# 549-addon.net
KiCad netlist of a schematic drawn in EAGLE
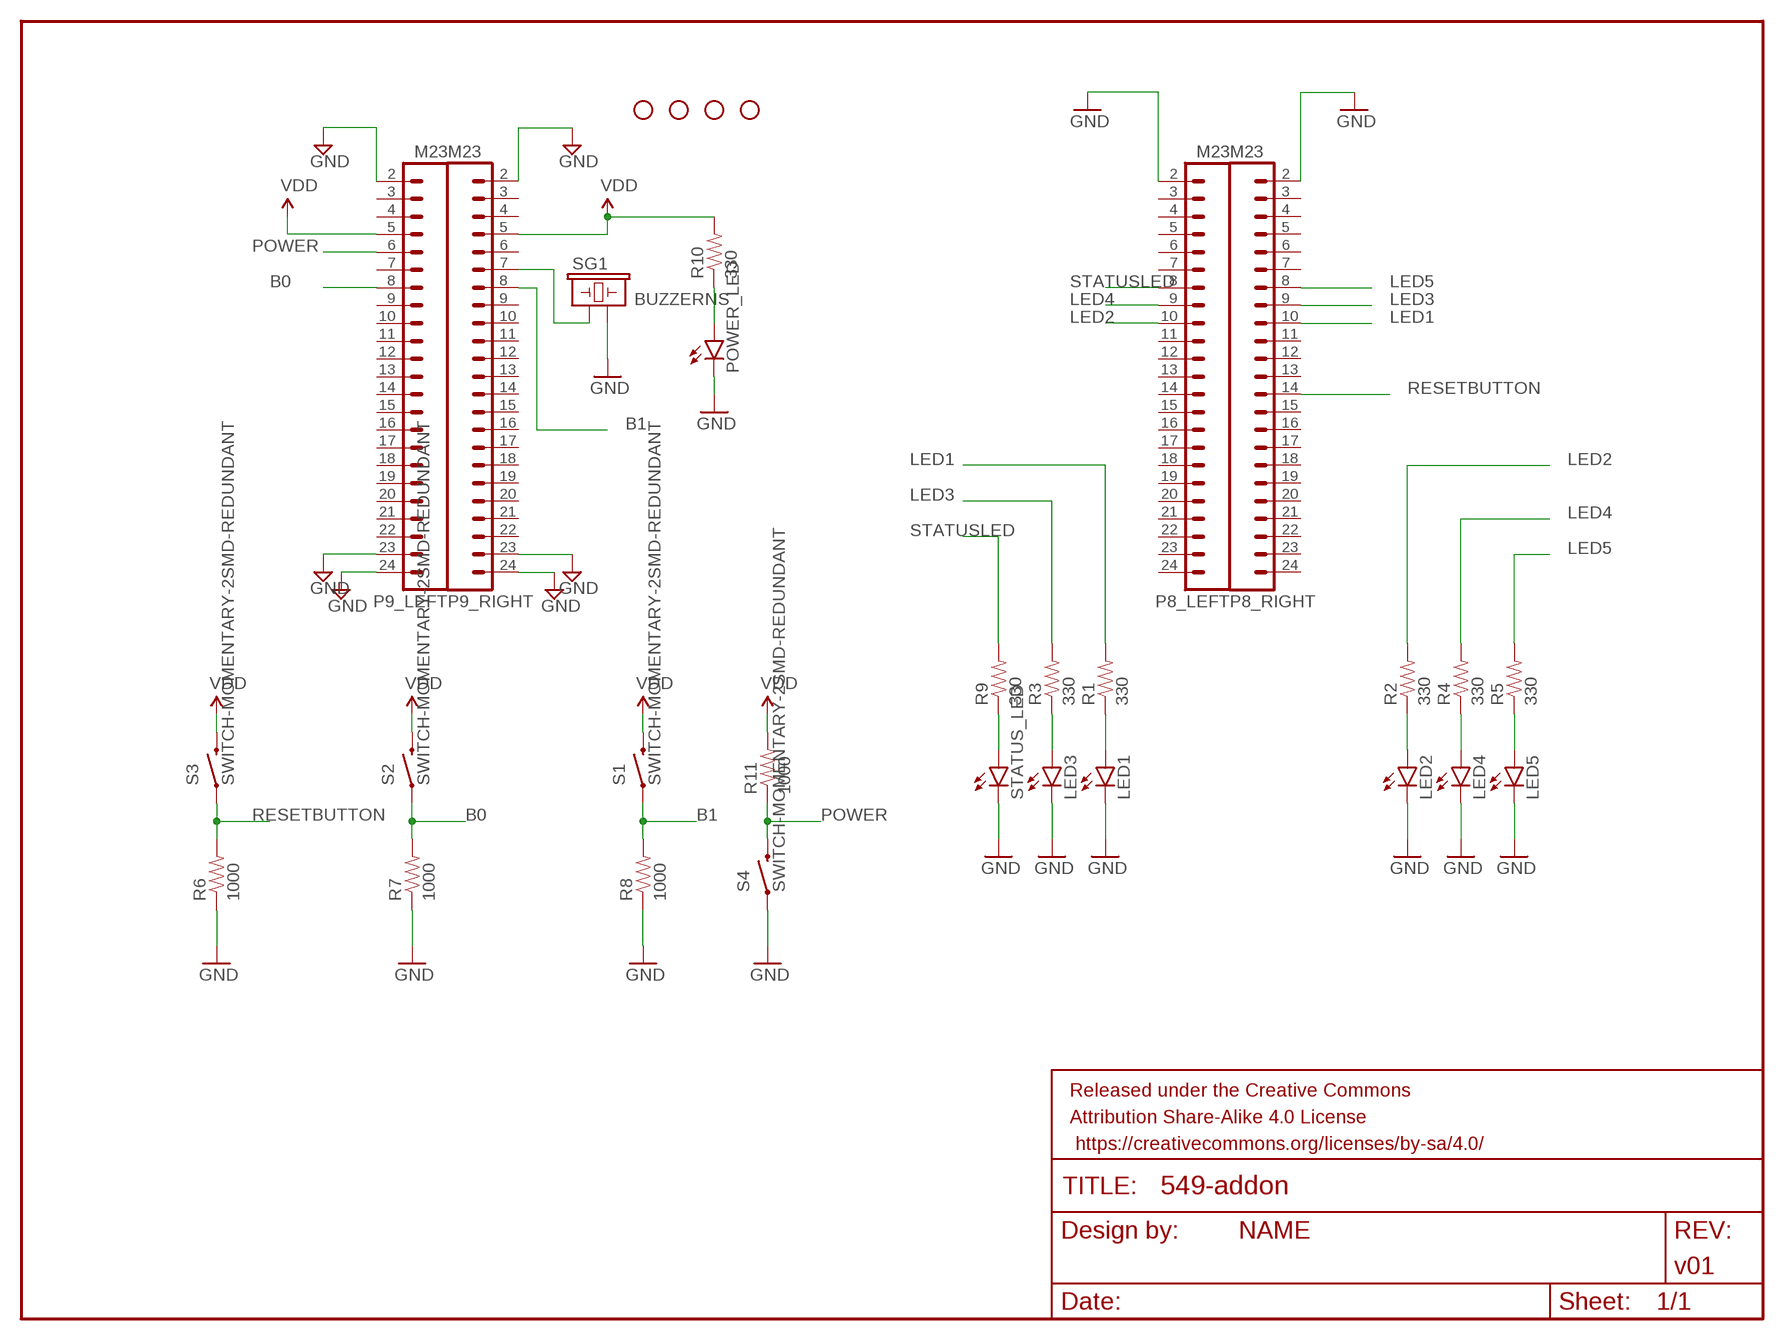
[diagram p0: schematic, sheet 1]

(export (version "E")
  (design (tool "Eeschema 10.0.6"))
  (components
    (comp (ref "FRAME1")
      (value "FRAME-LETTER")
      (footprint "eagle-import:CREATIVE_COMMONS")
      (fields (field (name "DESIGNER") "NAME"))
      (libsource (lib "eagle-import") (part "FRAME-LETTER"))
    )
    (comp (ref "LED1")
      (value "LED1206")
      (footprint "eagle-import:LED-1206")
      (libsource (lib "eagle-import") (part "LED1206"))
    )
    (comp (ref "LED2")
      (value "LED1206")
      (footprint "eagle-import:LED-1206")
      (libsource (lib "eagle-import") (part "LED1206"))
    )
    (comp (ref "LED3")
      (value "LED1206")
      (footprint "eagle-import:LED-1206")
      (libsource (lib "eagle-import") (part "LED1206"))
    )
    (comp (ref "LED4")
      (value "LED1206")
      (footprint "eagle-import:LED-1206")
      (libsource (lib "eagle-import") (part "LED1206"))
    )
    (comp (ref "LED5")
      (value "LED1206")
      (footprint "eagle-import:LED-1206")
      (libsource (lib "eagle-import") (part "LED1206"))
    )
    (comp (ref "P8_LEFT")
      (value "M23")
      (footprint "eagle-import:1X23")
      (libsource (lib "eagle-import") (part "M23"))
    )
    (comp (ref "P8_RIGHT")
      (value "M23")
      (footprint "eagle-import:1X23")
      (libsource (lib "eagle-import") (part "M23"))
    )
    (comp (ref "P9_LEFT")
      (value "M23")
      (footprint "eagle-import:1X23")
      (libsource (lib "eagle-import") (part "M23"))
    )
    (comp (ref "P9_RIGHT")
      (value "M23")
      (footprint "eagle-import:1X23")
      (libsource (lib "eagle-import") (part "M23"))
    )
    (comp (ref "POWER_LED")
      (value "LED1206")
      (footprint "eagle-import:LED-1206")
      (libsource (lib "eagle-import") (part "LED1206"))
    )
    (comp (ref "R1")
      (value "330")
      (footprint "eagle-import:1206")
      (libsource (lib "eagle-import") (part "RESISTOR1206"))
    )
    (comp (ref "R2")
      (value "330")
      (footprint "eagle-import:1206")
      (libsource (lib "eagle-import") (part "RESISTOR1206"))
    )
    (comp (ref "R3")
      (value "330")
      (footprint "eagle-import:1206")
      (libsource (lib "eagle-import") (part "RESISTOR1206"))
    )
    (comp (ref "R4")
      (value "330")
      (footprint "eagle-import:1206")
      (libsource (lib "eagle-import") (part "RESISTOR1206"))
    )
    (comp (ref "R5")
      (value "330")
      (footprint "eagle-import:1206")
      (libsource (lib "eagle-import") (part "RESISTOR1206"))
    )
    (comp (ref "R6")
      (value "1000")
      (footprint "eagle-import:1206")
      (libsource (lib "eagle-import") (part "RESISTOR1206"))
    )
    (comp (ref "R7")
      (value "1000")
      (footprint "eagle-import:1206")
      (libsource (lib "eagle-import") (part "RESISTOR1206"))
    )
    (comp (ref "R8")
      (value "1000")
      (footprint "eagle-import:1206")
      (libsource (lib "eagle-import") (part "RESISTOR1206"))
    )
    (comp (ref "R9")
      (value "330")
      (footprint "eagle-import:1206")
      (libsource (lib "eagle-import") (part "RESISTOR1206"))
    )
    (comp (ref "R10")
      (value "330")
      (footprint "eagle-import:1206")
      (libsource (lib "eagle-import") (part "RESISTOR1206"))
    )
    (comp (ref "R11")
      (value "1000")
      (footprint "eagle-import:1206")
      (libsource (lib "eagle-import") (part "RESISTOR1206"))
    )
    (comp (ref "S1")
      (value "SWITCH-MOMENTARY-2SMD-REDUNDANT")
      (footprint "eagle-import:TACTILE-SWITCH-SMD")
      (libsource (lib "eagle-import") (part "SWITCH-MOMENTARY-2SMD-REDUNDANT"))
    )
    (comp (ref "S2")
      (value "SWITCH-MOMENTARY-2SMD-REDUNDANT")
      (footprint "eagle-import:TACTILE-SWITCH-SMD")
      (libsource (lib "eagle-import") (part "SWITCH-MOMENTARY-2SMD-REDUNDANT"))
    )
    (comp (ref "S3")
      (value "SWITCH-MOMENTARY-2SMD-REDUNDANT")
      (footprint "eagle-import:TACTILE-SWITCH-SMD")
      (libsource (lib "eagle-import") (part "SWITCH-MOMENTARY-2SMD-REDUNDANT"))
    )
    (comp (ref "S4")
      (value "SWITCH-MOMENTARY-2SMD-REDUNDANT")
      (footprint "eagle-import:TACTILE-SWITCH-SMD")
      (libsource (lib "eagle-import") (part "SWITCH-MOMENTARY-2SMD-REDUNDANT"))
    )
    (comp (ref "SG1")
      (value "BUZZERNS")
      (footprint "eagle-import:BUZZER-12MM-NS")
      (libsource (lib "eagle-import") (part "BUZZERNS"))
    )
    (comp (ref "STANDOFF1")
      (value "STAND-OFF")
      (footprint "eagle-import:STAND-OFF")
      (libsource (lib "eagle-import") (part "STAND-OFF"))
    )
    (comp (ref "STANDOFF2")
      (value "STAND-OFF")
      (footprint "eagle-import:STAND-OFF")
      (libsource (lib "eagle-import") (part "STAND-OFF"))
    )
    (comp (ref "STANDOFF3")
      (value "STAND-OFF")
      (footprint "eagle-import:STAND-OFF")
      (libsource (lib "eagle-import") (part "STAND-OFF"))
    )
    (comp (ref "STANDOFF4")
      (value "STAND-OFF")
      (footprint "eagle-import:STAND-OFF")
      (libsource (lib "eagle-import") (part "STAND-OFF"))
    )
    (comp (ref "STATUS_LED")
      (value "LED1206")
      (footprint "eagle-import:LED-1206")
      (libsource (lib "eagle-import") (part "LED1206"))
    )
  )
  (nets
    (net (code "1") (name "/B0") (class "Default")
      (node (ref "P9_LEFT") (pin "8") (pinfunction "8_8") (pintype "passive"))
      (node (ref "R7") (pin "2") (pinfunction "2_2") (pintype "passive"))
      (node (ref "S2") (pin "1") (pinfunction "1_1") (pintype "passive"))
      (node (ref "S2") (pin "2") (pinfunction "1_2") (pintype "passive"))
    )
    (net (code "2") (name "/B1") (class "Default")
      (node (ref "P9_RIGHT") (pin "8") (pinfunction "8_8") (pintype "passive"))
      (node (ref "R8") (pin "2") (pinfunction "2_2") (pintype "passive"))
      (node (ref "S1") (pin "1") (pinfunction "1_1") (pintype "passive"))
      (node (ref "S1") (pin "2") (pinfunction "1_2") (pintype "passive"))
    )
    (net (code "3") (name "/LED1") (class "Default")
      (node (ref "P8_RIGHT") (pin "10") (pinfunction "10_10") (pintype "passive"))
      (node (ref "R1") (pin "2") (pinfunction "2_2") (pintype "passive"))
    )
    (net (code "4") (name "/LED2") (class "Default")
      (node (ref "P8_LEFT") (pin "10") (pinfunction "10_10") (pintype "passive"))
      (node (ref "R2") (pin "2") (pinfunction "2_2") (pintype "passive"))
    )
    (net (code "5") (name "/LED3") (class "Default")
      (node (ref "P8_RIGHT") (pin "9") (pinfunction "9_9") (pintype "passive"))
      (node (ref "R3") (pin "2") (pinfunction "2_2") (pintype "passive"))
    )
    (net (code "6") (name "/LED4") (class "Default")
      (node (ref "P8_LEFT") (pin "9") (pinfunction "9_9") (pintype "passive"))
      (node (ref "R4") (pin "2") (pinfunction "2_2") (pintype "passive"))
    )
    (net (code "7") (name "/LED5") (class "Default")
      (node (ref "P8_RIGHT") (pin "8") (pinfunction "8_8") (pintype "passive"))
      (node (ref "R5") (pin "2") (pinfunction "2_2") (pintype "passive"))
    )
    (net (code "8") (name "/POWER") (class "Default")
      (node (ref "P9_LEFT") (pin "6") (pinfunction "6_6") (pintype "passive"))
      (node (ref "R11") (pin "1") (pinfunction "1_1") (pintype "passive"))
      (node (ref "S4") (pin "3") (pinfunction "2_3") (pintype "passive"))
      (node (ref "S4") (pin "4") (pinfunction "2_4") (pintype "passive"))
    )
    (net (code "9") (name "/RESETBUTTON") (class "Default")
      (node (ref "P8_RIGHT") (pin "14") (pinfunction "14_14") (pintype "passive"))
      (node (ref "R6") (pin "2") (pinfunction "2_2") (pintype "passive"))
      (node (ref "S3") (pin "1") (pinfunction "1_1") (pintype "passive"))
      (node (ref "S3") (pin "2") (pinfunction "1_2") (pintype "passive"))
    )
    (net (code "10") (name "/STATUSLED") (class "Default")
      (node (ref "P8_LEFT") (pin "8") (pinfunction "8_8") (pintype "passive"))
      (node (ref "R9") (pin "2") (pinfunction "2_2") (pintype "passive"))
    )
    (net (code "11") (name "GND") (class "Default")
      (node (ref "LED1") (pin "C") (pinfunction "C_C") (pintype "passive"))
      (node (ref "LED2") (pin "C") (pinfunction "C_C") (pintype "passive"))
      (node (ref "LED3") (pin "C") (pinfunction "C_C") (pintype "passive"))
      (node (ref "LED4") (pin "C") (pinfunction "C_C") (pintype "passive"))
      (node (ref "LED5") (pin "C") (pinfunction "C_C") (pintype "passive"))
      (node (ref "P8_LEFT") (pin "2") (pinfunction "2_2") (pintype "passive"))
      (node (ref "P8_RIGHT") (pin "2") (pinfunction "2_2") (pintype "passive"))
      (node (ref "P9_LEFT") (pin "2") (pinfunction "2_2") (pintype "passive"))
      (node (ref "P9_LEFT") (pin "23") (pinfunction "23_23") (pintype "passive"))
      (node (ref "P9_LEFT") (pin "24") (pinfunction "24_24") (pintype "passive"))
      (node (ref "P9_RIGHT") (pin "2") (pinfunction "2_2") (pintype "passive"))
      (node (ref "P9_RIGHT") (pin "23") (pinfunction "23_23") (pintype "passive"))
      (node (ref "P9_RIGHT") (pin "24") (pinfunction "24_24") (pintype "passive"))
      (node (ref "POWER_LED") (pin "C") (pinfunction "C_C") (pintype "passive"))
      (node (ref "R6") (pin "1") (pinfunction "1_1") (pintype "passive"))
      (node (ref "R7") (pin "1") (pinfunction "1_1") (pintype "passive"))
      (node (ref "R8") (pin "1") (pinfunction "1_1") (pintype "passive"))
      (node (ref "S4") (pin "1") (pinfunction "1_1") (pintype "passive"))
      (node (ref "S4") (pin "2") (pinfunction "1_2") (pintype "passive"))
      (node (ref "SG1") (pin "-") (pinfunction "2_-") (pintype "passive"))
      (node (ref "STATUS_LED") (pin "C") (pinfunction "C_C") (pintype "passive"))
    )
    (net (code "12") (name "Net-(LED1-PadA)") (class "Default")
      (node (ref "LED1") (pin "A") (pinfunction "A_A") (pintype "passive"))
      (node (ref "R1") (pin "1") (pinfunction "1_1") (pintype "passive"))
    )
    (net (code "13") (name "Net-(LED2-PadA)") (class "Default")
      (node (ref "LED2") (pin "A") (pinfunction "A_A") (pintype "passive"))
      (node (ref "R2") (pin "1") (pinfunction "1_1") (pintype "passive"))
    )
    (net (code "14") (name "Net-(LED3-PadA)") (class "Default")
      (node (ref "LED3") (pin "A") (pinfunction "A_A") (pintype "passive"))
      (node (ref "R3") (pin "1") (pinfunction "1_1") (pintype "passive"))
    )
    (net (code "15") (name "Net-(LED4-PadA)") (class "Default")
      (node (ref "LED4") (pin "A") (pinfunction "A_A") (pintype "passive"))
      (node (ref "R4") (pin "1") (pinfunction "1_1") (pintype "passive"))
    )
    (net (code "16") (name "Net-(LED5-PadA)") (class "Default")
      (node (ref "LED5") (pin "A") (pinfunction "A_A") (pintype "passive"))
      (node (ref "R5") (pin "1") (pinfunction "1_1") (pintype "passive"))
    )
    (net (code "17") (name "Net-(POWER_LED-PadA)") (class "Default")
      (node (ref "POWER_LED") (pin "A") (pinfunction "A_A") (pintype "passive"))
      (node (ref "R10") (pin "1") (pinfunction "1_1") (pintype "passive"))
    )
    (net (code "18") (name "Net-(R9-Pad1)") (class "Default")
      (node (ref "R9") (pin "1") (pinfunction "1_1") (pintype "passive"))
      (node (ref "STATUS_LED") (pin "A") (pinfunction "A_A") (pintype "passive"))
    )
    (net (code "19") (name "Net-(SG1-1)") (class "Default")
      (node (ref "P9_RIGHT") (pin "7") (pinfunction "7_7") (pintype "passive"))
      (node (ref "SG1") (pin "+") (pinfunction "1_+") (pintype "passive"))
    )
    (net (code "20") (name "VDD") (class "Default")
      (node (ref "P9_LEFT") (pin "5") (pinfunction "5_5") (pintype "passive"))
      (node (ref "P9_RIGHT") (pin "5") (pinfunction "5_5") (pintype "passive"))
      (node (ref "R10") (pin "2") (pinfunction "2_2") (pintype "passive"))
      (node (ref "R11") (pin "2") (pinfunction "2_2") (pintype "passive"))
      (node (ref "S1") (pin "3") (pinfunction "2_3") (pintype "passive"))
      (node (ref "S1") (pin "4") (pinfunction "2_4") (pintype "passive"))
      (node (ref "S2") (pin "3") (pinfunction "2_3") (pintype "passive"))
      (node (ref "S2") (pin "4") (pinfunction "2_4") (pintype "passive"))
      (node (ref "S3") (pin "3") (pinfunction "2_3") (pintype "passive"))
      (node (ref "S3") (pin "4") (pinfunction "2_4") (pintype "passive"))
    )
    (net (code "21") (name "unconnected-(P8_LEFT-Pad3)") (class "Default")
      (node (ref "P8_LEFT") (pin "3") (pinfunction "3_3") (pintype "passive"))
    )
    (net (code "22") (name "unconnected-(P8_LEFT-Pad4)") (class "Default")
      (node (ref "P8_LEFT") (pin "4") (pinfunction "4_4") (pintype "passive"))
    )
    (net (code "23") (name "unconnected-(P8_LEFT-Pad5)") (class "Default")
      (node (ref "P8_LEFT") (pin "5") (pinfunction "5_5") (pintype "passive"))
    )
    (net (code "24") (name "unconnected-(P8_LEFT-Pad6)") (class "Default")
      (node (ref "P8_LEFT") (pin "6") (pinfunction "6_6") (pintype "passive"))
    )
    (net (code "25") (name "unconnected-(P8_LEFT-Pad7)") (class "Default")
      (node (ref "P8_LEFT") (pin "7") (pinfunction "7_7") (pintype "passive"))
    )
    (net (code "26") (name "unconnected-(P8_LEFT-Pad11)") (class "Default")
      (node (ref "P8_LEFT") (pin "11") (pinfunction "11_11") (pintype "passive"))
    )
    (net (code "27") (name "unconnected-(P8_LEFT-Pad12)") (class "Default")
      (node (ref "P8_LEFT") (pin "12") (pinfunction "12_12") (pintype "passive"))
    )
    (net (code "28") (name "unconnected-(P8_LEFT-Pad13)") (class "Default")
      (node (ref "P8_LEFT") (pin "13") (pinfunction "13_13") (pintype "passive"))
    )
    (net (code "29") (name "unconnected-(P8_LEFT-Pad14)") (class "Default")
      (node (ref "P8_LEFT") (pin "14") (pinfunction "14_14") (pintype "passive"))
    )
    (net (code "30") (name "unconnected-(P8_LEFT-Pad15)") (class "Default")
      (node (ref "P8_LEFT") (pin "15") (pinfunction "15_15") (pintype "passive"))
    )
    (net (code "31") (name "unconnected-(P8_LEFT-Pad16)") (class "Default")
      (node (ref "P8_LEFT") (pin "16") (pinfunction "16_16") (pintype "passive"))
    )
    (net (code "32") (name "unconnected-(P8_LEFT-Pad17)") (class "Default")
      (node (ref "P8_LEFT") (pin "17") (pinfunction "17_17") (pintype "passive"))
    )
    (net (code "33") (name "unconnected-(P8_LEFT-Pad18)") (class "Default")
      (node (ref "P8_LEFT") (pin "18") (pinfunction "18_18") (pintype "passive"))
    )
    (net (code "34") (name "unconnected-(P8_LEFT-Pad19)") (class "Default")
      (node (ref "P8_LEFT") (pin "19") (pinfunction "19_19") (pintype "passive"))
    )
    (net (code "35") (name "unconnected-(P8_LEFT-Pad20)") (class "Default")
      (node (ref "P8_LEFT") (pin "20") (pinfunction "20_20") (pintype "passive"))
    )
    (net (code "36") (name "unconnected-(P8_LEFT-Pad21)") (class "Default")
      (node (ref "P8_LEFT") (pin "21") (pinfunction "21_21") (pintype "passive"))
    )
    (net (code "37") (name "unconnected-(P8_LEFT-Pad22)") (class "Default")
      (node (ref "P8_LEFT") (pin "22") (pinfunction "22_22") (pintype "passive"))
    )
    (net (code "38") (name "unconnected-(P8_LEFT-Pad23)") (class "Default")
      (node (ref "P8_LEFT") (pin "23") (pinfunction "23_23") (pintype "passive"))
    )
    (net (code "39") (name "unconnected-(P8_LEFT-Pad24)") (class "Default")
      (node (ref "P8_LEFT") (pin "24") (pinfunction "24_24") (pintype "passive"))
    )
    (net (code "40") (name "unconnected-(P8_RIGHT-Pad3)") (class "Default")
      (node (ref "P8_RIGHT") (pin "3") (pinfunction "3_3") (pintype "passive"))
    )
    (net (code "41") (name "unconnected-(P8_RIGHT-Pad4)") (class "Default")
      (node (ref "P8_RIGHT") (pin "4") (pinfunction "4_4") (pintype "passive"))
    )
    (net (code "42") (name "unconnected-(P8_RIGHT-Pad5)") (class "Default")
      (node (ref "P8_RIGHT") (pin "5") (pinfunction "5_5") (pintype "passive"))
    )
    (net (code "43") (name "unconnected-(P8_RIGHT-Pad6)") (class "Default")
      (node (ref "P8_RIGHT") (pin "6") (pinfunction "6_6") (pintype "passive"))
    )
    (net (code "44") (name "unconnected-(P8_RIGHT-Pad7)") (class "Default")
      (node (ref "P8_RIGHT") (pin "7") (pinfunction "7_7") (pintype "passive"))
    )
    (net (code "45") (name "unconnected-(P8_RIGHT-Pad11)") (class "Default")
      (node (ref "P8_RIGHT") (pin "11") (pinfunction "11_11") (pintype "passive"))
    )
    (net (code "46") (name "unconnected-(P8_RIGHT-Pad12)") (class "Default")
      (node (ref "P8_RIGHT") (pin "12") (pinfunction "12_12") (pintype "passive"))
    )
    (net (code "47") (name "unconnected-(P8_RIGHT-Pad13)") (class "Default")
      (node (ref "P8_RIGHT") (pin "13") (pinfunction "13_13") (pintype "passive"))
    )
    (net (code "48") (name "unconnected-(P8_RIGHT-Pad15)") (class "Default")
      (node (ref "P8_RIGHT") (pin "15") (pinfunction "15_15") (pintype "passive"))
    )
    (net (code "49") (name "unconnected-(P8_RIGHT-Pad16)") (class "Default")
      (node (ref "P8_RIGHT") (pin "16") (pinfunction "16_16") (pintype "passive"))
    )
    (net (code "50") (name "unconnected-(P8_RIGHT-Pad17)") (class "Default")
      (node (ref "P8_RIGHT") (pin "17") (pinfunction "17_17") (pintype "passive"))
    )
    (net (code "51") (name "unconnected-(P8_RIGHT-Pad18)") (class "Default")
      (node (ref "P8_RIGHT") (pin "18") (pinfunction "18_18") (pintype "passive"))
    )
    (net (code "52") (name "unconnected-(P8_RIGHT-Pad19)") (class "Default")
      (node (ref "P8_RIGHT") (pin "19") (pinfunction "19_19") (pintype "passive"))
    )
    (net (code "53") (name "unconnected-(P8_RIGHT-Pad20)") (class "Default")
      (node (ref "P8_RIGHT") (pin "20") (pinfunction "20_20") (pintype "passive"))
    )
    (net (code "54") (name "unconnected-(P8_RIGHT-Pad21)") (class "Default")
      (node (ref "P8_RIGHT") (pin "21") (pinfunction "21_21") (pintype "passive"))
    )
    (net (code "55") (name "unconnected-(P8_RIGHT-Pad22)") (class "Default")
      (node (ref "P8_RIGHT") (pin "22") (pinfunction "22_22") (pintype "passive"))
    )
    (net (code "56") (name "unconnected-(P8_RIGHT-Pad23)") (class "Default")
      (node (ref "P8_RIGHT") (pin "23") (pinfunction "23_23") (pintype "passive"))
    )
    (net (code "57") (name "unconnected-(P8_RIGHT-Pad24)") (class "Default")
      (node (ref "P8_RIGHT") (pin "24") (pinfunction "24_24") (pintype "passive"))
    )
    (net (code "58") (name "unconnected-(P9_LEFT-Pad3)") (class "Default")
      (node (ref "P9_LEFT") (pin "3") (pinfunction "3_3") (pintype "passive"))
    )
    (net (code "59") (name "unconnected-(P9_LEFT-Pad4)") (class "Default")
      (node (ref "P9_LEFT") (pin "4") (pinfunction "4_4") (pintype "passive"))
    )
    (net (code "60") (name "unconnected-(P9_LEFT-Pad7)") (class "Default")
      (node (ref "P9_LEFT") (pin "7") (pinfunction "7_7") (pintype "passive"))
    )
    (net (code "61") (name "unconnected-(P9_LEFT-Pad9)") (class "Default")
      (node (ref "P9_LEFT") (pin "9") (pinfunction "9_9") (pintype "passive"))
    )
    (net (code "62") (name "unconnected-(P9_LEFT-Pad10)") (class "Default")
      (node (ref "P9_LEFT") (pin "10") (pinfunction "10_10") (pintype "passive"))
    )
    (net (code "63") (name "unconnected-(P9_LEFT-Pad11)") (class "Default")
      (node (ref "P9_LEFT") (pin "11") (pinfunction "11_11") (pintype "passive"))
    )
    (net (code "64") (name "unconnected-(P9_LEFT-Pad12)") (class "Default")
      (node (ref "P9_LEFT") (pin "12") (pinfunction "12_12") (pintype "passive"))
    )
    (net (code "65") (name "unconnected-(P9_LEFT-Pad13)") (class "Default")
      (node (ref "P9_LEFT") (pin "13") (pinfunction "13_13") (pintype "passive"))
    )
    (net (code "66") (name "unconnected-(P9_LEFT-Pad14)") (class "Default")
      (node (ref "P9_LEFT") (pin "14") (pinfunction "14_14") (pintype "passive"))
    )
    (net (code "67") (name "unconnected-(P9_LEFT-Pad15)") (class "Default")
      (node (ref "P9_LEFT") (pin "15") (pinfunction "15_15") (pintype "passive"))
    )
    (net (code "68") (name "unconnected-(P9_LEFT-Pad16)") (class "Default")
      (node (ref "P9_LEFT") (pin "16") (pinfunction "16_16") (pintype "passive"))
    )
    (net (code "69") (name "unconnected-(P9_LEFT-Pad17)") (class "Default")
      (node (ref "P9_LEFT") (pin "17") (pinfunction "17_17") (pintype "passive"))
    )
    (net (code "70") (name "unconnected-(P9_LEFT-Pad18)") (class "Default")
      (node (ref "P9_LEFT") (pin "18") (pinfunction "18_18") (pintype "passive"))
    )
    (net (code "71") (name "unconnected-(P9_LEFT-Pad19)") (class "Default")
      (node (ref "P9_LEFT") (pin "19") (pinfunction "19_19") (pintype "passive"))
    )
    (net (code "72") (name "unconnected-(P9_LEFT-Pad20)") (class "Default")
      (node (ref "P9_LEFT") (pin "20") (pinfunction "20_20") (pintype "passive"))
    )
    (net (code "73") (name "unconnected-(P9_LEFT-Pad21)") (class "Default")
      (node (ref "P9_LEFT") (pin "21") (pinfunction "21_21") (pintype "passive"))
    )
    (net (code "74") (name "unconnected-(P9_LEFT-Pad22)") (class "Default")
      (node (ref "P9_LEFT") (pin "22") (pinfunction "22_22") (pintype "passive"))
    )
    (net (code "75") (name "unconnected-(P9_RIGHT-Pad3)") (class "Default")
      (node (ref "P9_RIGHT") (pin "3") (pinfunction "3_3") (pintype "passive"))
    )
    (net (code "76") (name "unconnected-(P9_RIGHT-Pad4)") (class "Default")
      (node (ref "P9_RIGHT") (pin "4") (pinfunction "4_4") (pintype "passive"))
    )
    (net (code "77") (name "unconnected-(P9_RIGHT-Pad6)") (class "Default")
      (node (ref "P9_RIGHT") (pin "6") (pinfunction "6_6") (pintype "passive"))
    )
    (net (code "78") (name "unconnected-(P9_RIGHT-Pad9)") (class "Default")
      (node (ref "P9_RIGHT") (pin "9") (pinfunction "9_9") (pintype "passive"))
    )
    (net (code "79") (name "unconnected-(P9_RIGHT-Pad10)") (class "Default")
      (node (ref "P9_RIGHT") (pin "10") (pinfunction "10_10") (pintype "passive"))
    )
    (net (code "80") (name "unconnected-(P9_RIGHT-Pad11)") (class "Default")
      (node (ref "P9_RIGHT") (pin "11") (pinfunction "11_11") (pintype "passive"))
    )
    (net (code "81") (name "unconnected-(P9_RIGHT-Pad12)") (class "Default")
      (node (ref "P9_RIGHT") (pin "12") (pinfunction "12_12") (pintype "passive"))
    )
    (net (code "82") (name "unconnected-(P9_RIGHT-Pad13)") (class "Default")
      (node (ref "P9_RIGHT") (pin "13") (pinfunction "13_13") (pintype "passive"))
    )
    (net (code "83") (name "unconnected-(P9_RIGHT-Pad14)") (class "Default")
      (node (ref "P9_RIGHT") (pin "14") (pinfunction "14_14") (pintype "passive"))
    )
    (net (code "84") (name "unconnected-(P9_RIGHT-Pad15)") (class "Default")
      (node (ref "P9_RIGHT") (pin "15") (pinfunction "15_15") (pintype "passive"))
    )
    (net (code "85") (name "unconnected-(P9_RIGHT-Pad16)") (class "Default")
      (node (ref "P9_RIGHT") (pin "16") (pinfunction "16_16") (pintype "passive"))
    )
    (net (code "86") (name "unconnected-(P9_RIGHT-Pad17)") (class "Default")
      (node (ref "P9_RIGHT") (pin "17") (pinfunction "17_17") (pintype "passive"))
    )
    (net (code "87") (name "unconnected-(P9_RIGHT-Pad18)") (class "Default")
      (node (ref "P9_RIGHT") (pin "18") (pinfunction "18_18") (pintype "passive"))
    )
    (net (code "88") (name "unconnected-(P9_RIGHT-Pad19)") (class "Default")
      (node (ref "P9_RIGHT") (pin "19") (pinfunction "19_19") (pintype "passive"))
    )
    (net (code "89") (name "unconnected-(P9_RIGHT-Pad20)") (class "Default")
      (node (ref "P9_RIGHT") (pin "20") (pinfunction "20_20") (pintype "passive"))
    )
    (net (code "90") (name "unconnected-(P9_RIGHT-Pad21)") (class "Default")
      (node (ref "P9_RIGHT") (pin "21") (pinfunction "21_21") (pintype "passive"))
    )
    (net (code "91") (name "unconnected-(P9_RIGHT-Pad22)") (class "Default")
      (node (ref "P9_RIGHT") (pin "22") (pinfunction "22_22") (pintype "passive"))
    )
  )
)
